# PIC_Trainer_16F.net
KiCad netlist of a schematic drawn in EAGLE
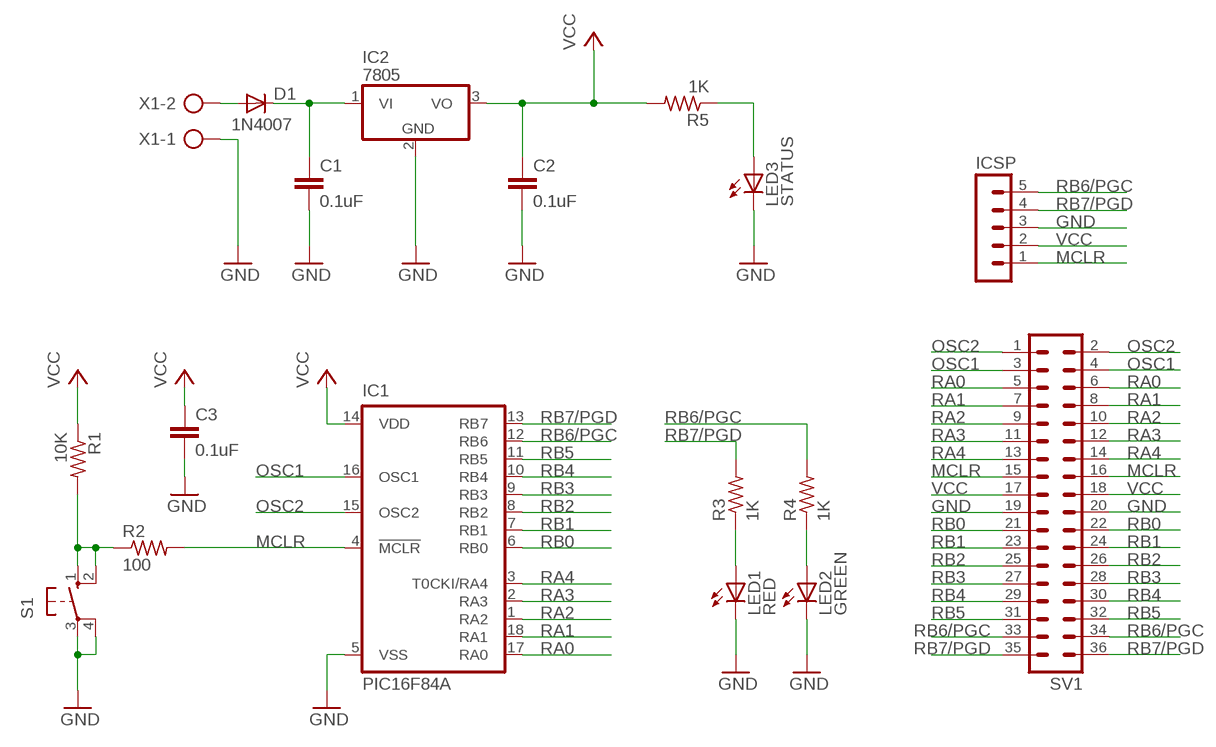
[diagram p0: schematic, sheet 1]

(export (version "E")
  (design (tool "Eeschema 10.0.6"))
  (components
    (comp (ref "C1")
      (value "0.1uF")
      (footprint "eagle-import:C050-025X075")
      (libsource (lib "eagle-import") (part "C-EU050-025X075"))
    )
    (comp (ref "C2")
      (value "0.1uF")
      (footprint "eagle-import:C050-025X075")
      (libsource (lib "eagle-import") (part "C-EU050-025X075"))
    )
    (comp (ref "C3")
      (value "0.1uF")
      (footprint "eagle-import:C050-025X075")
      (libsource (lib "eagle-import") (part "C-EU050-025X075"))
    )
    (comp (ref "D1")
      (value "1N4007")
      (footprint "eagle-import:DO41-10")
      (libsource (lib "eagle-import") (part "1N4004"))
    )
    (comp (ref "IC1")
      (value "PIC16F84A")
      (footprint "eagle-import:DIL18")
      (fields (field (name "MF") "MICROCHIP") (field (name "MPN") "PIC16F84A-04I/P"))
      (libsource (lib "eagle-import") (part "PIC16F8P4A"))
    )
    (comp (ref "IC2")
      (value "7805")
      (footprint "eagle-import:TO220H")
      (libsource (lib "eagle-import") (part "78T05"))
    )
    (comp (ref "ICSP")
      (value "MA05-1")
      (footprint "eagle-import:MA05-1")
      (libsource (lib "eagle-import") (part "MA05-1"))
    )
    (comp (ref "LED1")
      (value "RED")
      (footprint "eagle-import:LED5MM")
      (libsource (lib "eagle-import") (part "LED5MM"))
    )
    (comp (ref "LED2")
      (value "GREEN")
      (footprint "eagle-import:LED5MM")
      (libsource (lib "eagle-import") (part "LED5MM"))
    )
    (comp (ref "LED3")
      (value "STATUS")
      (footprint "eagle-import:LED5MM")
      (libsource (lib "eagle-import") (part "LED5MM"))
    )
    (comp (ref "R1")
      (value "10K")
      (footprint "eagle-import:0207_7")
      (libsource (lib "eagle-import") (part "R-US_0207/7"))
    )
    (comp (ref "R2")
      (value "100")
      (footprint "eagle-import:0207_7")
      (libsource (lib "eagle-import") (part "R-US_0207/7"))
    )
    (comp (ref "R3")
      (value "1K")
      (footprint "eagle-import:0207_7")
      (libsource (lib "eagle-import") (part "R-US_0207/7"))
    )
    (comp (ref "R4")
      (value "1K")
      (footprint "eagle-import:0207_7")
      (libsource (lib "eagle-import") (part "R-US_0207/7"))
    )
    (comp (ref "R5")
      (value "1K")
      (footprint "eagle-import:0207_7")
      (libsource (lib "eagle-import") (part "R-US_0207/7"))
    )
    (comp (ref "S1")
      (value "10-XX")
      (footprint "eagle-import:B3F-10XX")
      (fields (field (name "MPN") "B3F-1000"))
      (libsource (lib "eagle-import") (part "10-XX"))
    )
    (comp (ref "SV1")
      (value "MA18-2")
      (footprint "eagle-import:MA18-2")
      (libsource (lib "eagle-import") (part "MA18-2"))
    )
    (comp (ref "X1")
      (value "AK500/2-H")
      (footprint "eagle-import:AK500_2-H")
      (libsource (lib "eagle-import") (part "AK500/2-H"))
    )
  )
  (nets
    (net (code "1") (name "/MCLR") (class "Default")
      (node (ref "IC1") (pin "4") (pinfunction "~{MCLR}_4") (pintype "input"))
      (node (ref "ICSP") (pin "1") (pinfunction "1_1") (pintype "passive"))
      (node (ref "R2") (pin "2") (pinfunction "2_2") (pintype "passive"))
      (node (ref "SV1") (pin "15") (pinfunction "15_15") (pintype "passive"))
      (node (ref "SV1") (pin "16") (pinfunction "16_16") (pintype "passive"))
    )
    (net (code "2") (name "/OSC1") (class "Default")
      (node (ref "IC1") (pin "16") (pinfunction "OSC1_16") (pintype "input"))
      (node (ref "SV1") (pin "3") (pinfunction "3_3") (pintype "passive"))
      (node (ref "SV1") (pin "4") (pinfunction "4_4") (pintype "passive"))
    )
    (net (code "3") (name "/OSC2") (class "Default")
      (node (ref "IC1") (pin "15") (pinfunction "OSC2_15") (pintype "output"))
      (node (ref "SV1") (pin "1") (pinfunction "1_1") (pintype "passive"))
      (node (ref "SV1") (pin "2") (pinfunction "2_2") (pintype "passive"))
    )
    (net (code "4") (name "/RA0") (class "Default")
      (node (ref "IC1") (pin "17") (pinfunction "RA0_17") (pintype "bidirectional"))
      (node (ref "SV1") (pin "5") (pinfunction "5_5") (pintype "passive"))
      (node (ref "SV1") (pin "6") (pinfunction "6_6") (pintype "passive"))
    )
    (net (code "5") (name "/RA1") (class "Default")
      (node (ref "IC1") (pin "18") (pinfunction "RA1_18") (pintype "bidirectional"))
      (node (ref "SV1") (pin "7") (pinfunction "7_7") (pintype "passive"))
      (node (ref "SV1") (pin "8") (pinfunction "8_8") (pintype "passive"))
    )
    (net (code "6") (name "/RA2") (class "Default")
      (node (ref "IC1") (pin "1") (pinfunction "RA2_1") (pintype "bidirectional"))
      (node (ref "SV1") (pin "10") (pinfunction "10_10") (pintype "passive"))
      (node (ref "SV1") (pin "9") (pinfunction "9_9") (pintype "passive"))
    )
    (net (code "7") (name "/RA3") (class "Default")
      (node (ref "IC1") (pin "2") (pinfunction "RA3_2") (pintype "bidirectional"))
      (node (ref "SV1") (pin "11") (pinfunction "11_11") (pintype "passive"))
      (node (ref "SV1") (pin "12") (pinfunction "12_12") (pintype "passive"))
    )
    (net (code "8") (name "/RA4") (class "Default")
      (node (ref "IC1") (pin "3") (pinfunction "T0CKI/RA4_3") (pintype "bidirectional"))
      (node (ref "SV1") (pin "13") (pinfunction "13_13") (pintype "passive"))
      (node (ref "SV1") (pin "14") (pinfunction "14_14") (pintype "passive"))
    )
    (net (code "9") (name "/RB0") (class "Default")
      (node (ref "IC1") (pin "6") (pinfunction "RB0_6") (pintype "bidirectional"))
      (node (ref "SV1") (pin "21") (pinfunction "21_21") (pintype "passive"))
      (node (ref "SV1") (pin "22") (pinfunction "22_22") (pintype "passive"))
    )
    (net (code "10") (name "/RB1") (class "Default")
      (node (ref "IC1") (pin "7") (pinfunction "RB1_7") (pintype "bidirectional"))
      (node (ref "SV1") (pin "23") (pinfunction "23_23") (pintype "passive"))
      (node (ref "SV1") (pin "24") (pinfunction "24_24") (pintype "passive"))
    )
    (net (code "11") (name "/RB2") (class "Default")
      (node (ref "IC1") (pin "8") (pinfunction "RB2_8") (pintype "bidirectional"))
      (node (ref "SV1") (pin "25") (pinfunction "25_25") (pintype "passive"))
      (node (ref "SV1") (pin "26") (pinfunction "26_26") (pintype "passive"))
    )
    (net (code "12") (name "/RB3") (class "Default")
      (node (ref "IC1") (pin "9") (pinfunction "RB3_9") (pintype "bidirectional"))
      (node (ref "SV1") (pin "27") (pinfunction "27_27") (pintype "passive"))
      (node (ref "SV1") (pin "28") (pinfunction "28_28") (pintype "passive"))
    )
    (net (code "13") (name "/RB4") (class "Default")
      (node (ref "IC1") (pin "10") (pinfunction "RB4_10") (pintype "bidirectional"))
      (node (ref "SV1") (pin "29") (pinfunction "29_29") (pintype "passive"))
      (node (ref "SV1") (pin "30") (pinfunction "30_30") (pintype "passive"))
    )
    (net (code "14") (name "/RB5") (class "Default")
      (node (ref "IC1") (pin "11") (pinfunction "RB5_11") (pintype "bidirectional"))
      (node (ref "SV1") (pin "31") (pinfunction "31_31") (pintype "passive"))
      (node (ref "SV1") (pin "32") (pinfunction "32_32") (pintype "passive"))
    )
    (net (code "15") (name "/RB6{slash}PGC") (class "Default")
      (node (ref "IC1") (pin "12") (pinfunction "RB6_12") (pintype "bidirectional"))
      (node (ref "ICSP") (pin "5") (pinfunction "5_5") (pintype "passive"))
      (node (ref "R4") (pin "2") (pinfunction "2_2") (pintype "passive"))
      (node (ref "SV1") (pin "33") (pinfunction "33_33") (pintype "passive"))
      (node (ref "SV1") (pin "34") (pinfunction "34_34") (pintype "passive"))
    )
    (net (code "16") (name "/RB7{slash}PGD") (class "Default")
      (node (ref "IC1") (pin "13") (pinfunction "RB7_13") (pintype "bidirectional"))
      (node (ref "ICSP") (pin "4") (pinfunction "4_4") (pintype "passive"))
      (node (ref "R3") (pin "2") (pinfunction "2_2") (pintype "passive"))
      (node (ref "SV1") (pin "35") (pinfunction "35_35") (pintype "passive"))
      (node (ref "SV1") (pin "36") (pinfunction "36_36") (pintype "passive"))
    )
    (net (code "17") (name "GND") (class "Default")
      (node (ref "C1") (pin "2") (pinfunction "2_2") (pintype "passive"))
      (node (ref "C2") (pin "2") (pinfunction "2_2") (pintype "passive"))
      (node (ref "C3") (pin "2") (pinfunction "2_2") (pintype "passive"))
      (node (ref "IC1") (pin "5") (pinfunction "VSS_5") (pintype "power_in"))
      (node (ref "IC2") (pin "2") (pinfunction "GND_2") (pintype "passive"))
      (node (ref "ICSP") (pin "3") (pinfunction "3_3") (pintype "passive"))
      (node (ref "LED1") (pin "K") (pinfunction "C_K") (pintype "passive"))
      (node (ref "LED2") (pin "K") (pinfunction "C_K") (pintype "passive"))
      (node (ref "LED3") (pin "K") (pinfunction "C_K") (pintype "passive"))
      (node (ref "S1") (pin "3") (pinfunction "P_3") (pintype "passive"))
      (node (ref "S1") (pin "4") (pinfunction "P1_4") (pintype "passive"))
      (node (ref "SV1") (pin "19") (pinfunction "19_19") (pintype "passive"))
      (node (ref "SV1") (pin "20") (pinfunction "20_20") (pintype "passive"))
      (node (ref "X1") (pin "1") (pinfunction "KL_1") (pintype "passive"))
    )
    (net (code "18") (name "Net-(IC2-VI)") (class "Default")
      (node (ref "C1") (pin "1") (pinfunction "1_1") (pintype "passive"))
      (node (ref "D1") (pin "C") (pinfunction "C_C") (pintype "passive"))
      (node (ref "IC2") (pin "1") (pinfunction "VI_1") (pintype "input"))
    )
    (net (code "19") (name "Net-(LED1-PadA)") (class "Default")
      (node (ref "LED1") (pin "A") (pinfunction "A_A") (pintype "passive"))
      (node (ref "R3") (pin "1") (pinfunction "1_1") (pintype "passive"))
    )
    (net (code "20") (name "Net-(LED2-PadA)") (class "Default")
      (node (ref "LED2") (pin "A") (pinfunction "A_A") (pintype "passive"))
      (node (ref "R4") (pin "1") (pinfunction "1_1") (pintype "passive"))
    )
    (net (code "21") (name "Net-(LED3-PadA)") (class "Default")
      (node (ref "LED3") (pin "A") (pinfunction "A_A") (pintype "passive"))
      (node (ref "R5") (pin "1") (pinfunction "1_1") (pintype "passive"))
    )
    (net (code "22") (name "Net-(S1-S)") (class "Default")
      (node (ref "R1") (pin "2") (pinfunction "2_2") (pintype "passive"))
      (node (ref "R2") (pin "1") (pinfunction "1_1") (pintype "passive"))
      (node (ref "S1") (pin "1") (pinfunction "S_1") (pintype "passive"))
      (node (ref "S1") (pin "2") (pinfunction "S1_2") (pintype "passive"))
    )
    (net (code "23") (name "Net-(X1B-KL)") (class "Default")
      (node (ref "D1") (pin "A") (pinfunction "A_A") (pintype "passive"))
      (node (ref "X1") (pin "2") (pinfunction "KL_2") (pintype "passive"))
    )
    (net (code "24") (name "VCC") (class "Default")
      (node (ref "C2") (pin "1") (pinfunction "1_1") (pintype "passive"))
      (node (ref "C3") (pin "1") (pinfunction "1_1") (pintype "passive"))
      (node (ref "IC1") (pin "14") (pinfunction "VDD_14") (pintype "power_in"))
      (node (ref "IC2") (pin "3") (pinfunction "VO_3") (pintype "passive"))
      (node (ref "ICSP") (pin "2") (pinfunction "2_2") (pintype "passive"))
      (node (ref "R1") (pin "1") (pinfunction "1_1") (pintype "passive"))
      (node (ref "R5") (pin "2") (pinfunction "2_2") (pintype "passive"))
      (node (ref "SV1") (pin "17") (pinfunction "17_17") (pintype "passive"))
      (node (ref "SV1") (pin "18") (pinfunction "18_18") (pintype "passive"))
    )
  )
)
